# Main.net
KiCad netlist of a schematic drawn in Altium Designer
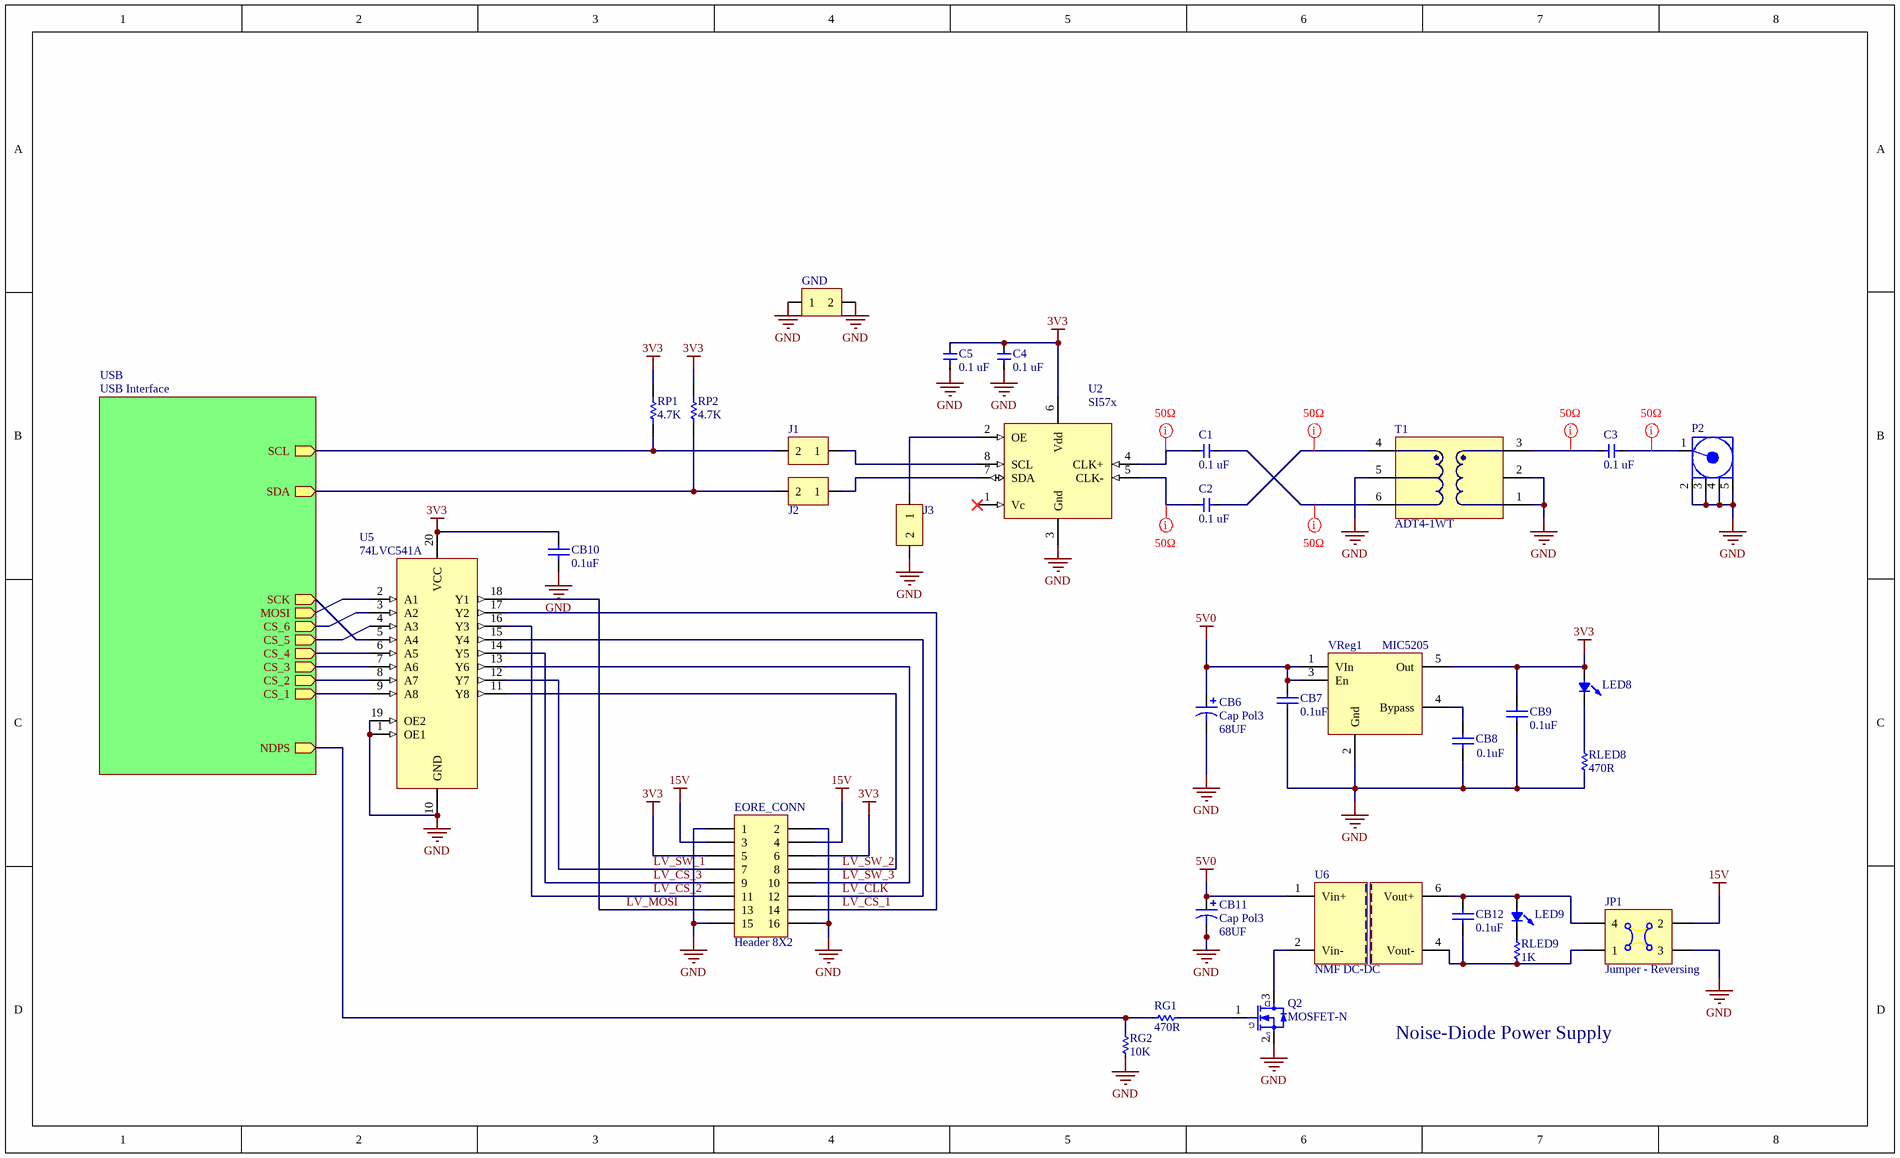
[diagram p0: Main.SchDoc]

(export (version "E")
  (design (tool "Eeschema 10.0.6"))
  (components
    (comp (ref "C1")
      (value "0.1 uF")
      (footprint "0603C")
      (description "SMT Cap")
      (fields (field (name "PUBLISHER") "Altium Limited"))
      (libsource (lib "Miscellaneous Devices") (part "Cap - SMT Small"))
    )
    (comp (ref "C2")
      (value "0.1 uF")
      (footprint "0603C")
      (description "SMT Cap")
      (fields (field (name "PUBLISHER") "Altium Limited"))
      (libsource (lib "Miscellaneous Devices") (part "Cap - SMT Small"))
    )
    (comp (ref "C3")
      (value "0.1 uF")
      (footprint "0603C")
      (description "SMT Cap")
      (fields (field (name "PUBLISHER") "Altium Limited"))
      (libsource (lib "Miscellaneous Devices") (part "Cap - SMT Small"))
    )
    (comp (ref "C4")
      (value "0.1 uF")
      (footprint "0603C")
      (description "SMT Cap")
      (fields (field (name "PUBLISHER") "Altium Limited"))
      (libsource (lib "Miscellaneous Devices") (part "Cap - SMT Small"))
    )
    (comp (ref "C5")
      (value "0.1 uF")
      (footprint "0603C")
      (description "SMT Cap")
      (fields (field (name "PUBLISHER") "Altium Limited"))
      (libsource (lib "Miscellaneous Devices") (part "Cap - SMT Small"))
    )
    (comp (ref "CB6")
      (value "Cap Pol3")
      (footprint "V")
      (description "KEMET T520 KO-CAP  Polymer SMT Tantalum")
      (fields (field (name "ALTIUM_VALUE") "68UF") (field (name "VOLTAGE") "10V"))
      (libsource (lib "Miscellaneous Devices") (part "Cap Pol3"))
    )
    (comp (ref "CB7")
      (value "0.1uF")
      (footprint "0603C")
      (description "Capacitor (Semiconductor SIM Model)")
      (fields (field (name "Comment") "Cap Semi") (field (name "PUBLISHER") "Altium Limited"))
      (libsource (lib "Miscellaneous Devices") (part "Cap Semi"))
    )
    (comp (ref "CB8")
      (value "0.1uF")
      (footprint "0603C")
      (description "Capacitor (Semiconductor SIM Model)")
      (fields (field (name "Comment") "Cap Semi") (field (name "PUBLISHER") "Altium Limited"))
      (libsource (lib "Miscellaneous Devices") (part "Cap Semi"))
    )
    (comp (ref "CB9")
      (value "0.1uF")
      (footprint "0603C")
      (description "Capacitor (Semiconductor SIM Model)")
      (fields (field (name "Comment") "Cap Semi") (field (name "PUBLISHER") "Altium Limited"))
      (libsource (lib "Miscellaneous Devices") (part "Cap Semi"))
    )
    (comp (ref "CB10")
      (value "0.1uF")
      (footprint "0603C")
      (description "Capacitor (Semiconductor SIM Model)")
      (fields (field (name "Comment") "Cap Semi") (field (name "PUBLISHER") "Altium Limited"))
      (libsource (lib "Miscellaneous Devices") (part "Cap Semi"))
    )
    (comp (ref "CB11")
      (value "Cap Pol3")
      (footprint "V")
      (description "KEMET T520 KO-CAP  Polymer SMT Tantalum")
      (fields (field (name "ALTIUM_VALUE") "68UF") (field (name "VOLTAGE") "10V"))
      (libsource (lib "Miscellaneous Devices") (part "Cap Pol3"))
    )
    (comp (ref "CB12")
      (value "0.1uF")
      (footprint "0603C")
      (description "Capacitor (Semiconductor SIM Model)")
      (fields (field (name "Comment") "Cap Semi") (field (name "PUBLISHER") "Altium Limited"))
      (libsource (lib "Miscellaneous Devices") (part "Cap Semi"))
    )
    (comp (ref "EORE_CONN")
      (value "Header 8X2")
      (footprint "SMT 16-pin rectangular header")
      (description "Header, 8-Pin, Dual row")
      (fields (field (name "PUBLISHER") "Altium Limited"))
      (libsource (lib "Miscellaneous Connectors") (part "Header 8X2"))
    )
    (comp (ref "GND")
      (value "Jumper")
      (footprint "HDR1X2")
      (description "Jumper - 2-Pin")
      (fields (field (name "PUBLISHER") "Altium Limited"))
      (libsource (lib "") (part "Jumper - 2 Pin_1"))
    )
    (comp (ref "J1")
      (value "Jumper")
      (footprint "HDR1X2")
      (description "Jumper - 2-Pin")
      (fields (field (name "PUBLISHER") "Altium Limited"))
      (libsource (lib "") (part "Jumper - 2 Pin_2"))
    )
    (comp (ref "J2")
      (value "Jumper")
      (footprint "HDR1X2")
      (description "Jumper - 2-Pin")
      (fields (field (name "PUBLISHER") "Altium Limited"))
      (libsource (lib "") (part "Jumper - 2 Pin_2"))
    )
    (comp (ref "J3")
      (value "Jumper")
      (footprint "HDR1X2")
      (description "Jumper - 2-Pin")
      (fields (field (name "PUBLISHER") "Altium Limited"))
      (libsource (lib "Miscellaneous Connectors") (part "Jumper - 2 Pin"))
    )
    (comp (ref "JP1")
      (value "Jumper - Reversing")
      (footprint "HDR2X2")
      (description "Reversing Jumper")
      (fields (field (name "PUBLISHER") "Altium Limited"))
      (libsource (lib "Miscellaneous Connectors") (part "Jumper - Reversing"))
    )
    (comp (ref "LED8")
      (value "LED0")
      (footprint "T1 LED")
      (description "T 1 3/4 LED")
      (fields (field (name "PUBLISHER") "Altium Limited"))
      (libsource (lib "Miscellaneous Devices") (part "LED0"))
    )
    (comp (ref "LED9")
      (value "LED0")
      (footprint "T1 LED")
      (description "T 1 3/4 LED")
      (fields (field (name "PUBLISHER") "Altium Limited"))
      (libsource (lib "Miscellaneous Devices") (part "LED0"))
    )
    (comp (ref "P2")
      (value "COAX-M")
      (footprint "SMA Jack - PCB Edge - MultiSize")
      (description "RF Coaxial PCB Connector, MMCX; Thru-Hole, Vertical Mount Plug,  50 Ohm Impedance")
      (fields (field (name "PUBLISHER") "Altium Limited"))
      (libsource (lib "Miscellaneous Connectors") (part "COAX-M"))
    )
    (comp (ref "Q2")
      (value "MOSFET-N")
      (footprint "SOT23-3N")
      (description "N-Channel MOSFET")
      (fields (field (name "PUBLISHER") "Altium Limited"))
      (libsource (lib "Miscellaneous Devices") (part "MOSFET-N"))
    )
    (comp (ref "RG1")
      (value "470R")
      (footprint "0603R")
      (description "Semiconductor Resistor")
      (fields (field (name "Comment") "Res Semi Small") (field (name "PUBLISHER") "Altium Limited"))
      (libsource (lib "Miscellaneous Devices") (part "Res Semi Small"))
    )
    (comp (ref "RG2")
      (value "10K")
      (footprint "0603R")
      (description "Semiconductor Resistor")
      (fields (field (name "Comment") "Res Semi Small") (field (name "PUBLISHER") "Altium Limited"))
      (libsource (lib "Miscellaneous Devices") (part "Res Semi Small"))
    )
    (comp (ref "RLED8")
      (value "470R")
      (footprint "0603R")
      (description "Semiconductor Resistor")
      (fields (field (name "Comment") "Res Semi Small") (field (name "PUBLISHER") "Altium Limited"))
      (libsource (lib "Miscellaneous Devices") (part "Res Semi Small"))
    )
    (comp (ref "RLED9")
      (value "1K")
      (footprint "0603R")
      (description "Semiconductor Resistor")
      (fields (field (name "Comment") "Res Semi Small") (field (name "PUBLISHER") "Altium Limited"))
      (libsource (lib "Miscellaneous Devices") (part "Res Semi Small"))
    )
    (comp (ref "RP1")
      (value "4.7K")
      (footprint "0603R")
      (description "Semiconductor Resistor")
      (fields (field (name "Comment") "Res Semi") (field (name "PUBLISHER") "Altium Limited"))
      (libsource (lib "Miscellaneous Devices") (part "Res Semi"))
    )
    (comp (ref "RP2")
      (value "4.7K")
      (footprint "0603R")
      (description "Semiconductor Resistor")
      (fields (field (name "Comment") "Res Semi") (field (name "PUBLISHER") "Altium Limited"))
      (libsource (lib "Miscellaneous Devices") (part "Res Semi"))
    )
    (comp (ref "T1")
      (value "ADT4-1WT")
      (footprint "CD542")
      (description "Surface Mount RF Transformer")
      (libsource (lib "RF Components") (part "ADT4-1WT"))
    )
    (comp (ref "U2")
      (value "SI57x")
      (footprint "SI57x")
      (description "10 MHZ TO 1.4 GHZ I2C PROGRAMMABLE XO/VCXO")
      (libsource (lib "RF Components") (part "SI570"))
    )
    (comp (ref "U5")
      (value "74LVC541A")
      (footprint "SOP65P780-20AN")
      (description "Octal buffer/line driver with 5 V tolerant inputs/outputs; 3-state")
      (libsource (lib "ICs") (part "74LVC541A"))
    )
    (comp (ref "U6")
      (value "NMF DC-DC")
      (footprint "SIL-6(A1)")
      (description "Murata NMF DC-DC - 1W, Single output")
      (libsource (lib "Unsorted") (part "Murata NMF DC-DC"))
    )
    (comp (ref "VReg1")
      (value "MIC5205")
      (footprint "SOT23-5AN")
      (description "150mA Low-Noise LDO Regulator")
      (libsource (lib "DAQ System") (part "MIC5205"))
    )
  )
  (nets
    (net (code "1") (name "/CS_1") (class "Default")
      (node (ref "U5") (pin "9") (pinfunction "A8_9") (pintype "input"))
    )
    (net (code "2") (name "/CS_2") (class "Default")
      (node (ref "U5") (pin "8") (pinfunction "A7_8") (pintype "input"))
    )
    (net (code "3") (name "/CS_3") (class "Default")
      (node (ref "U5") (pin "7") (pinfunction "A6_7") (pintype "input"))
    )
    (net (code "4") (name "/CS_4") (class "Default")
      (node (ref "U5") (pin "6") (pinfunction "A5_6") (pintype "input"))
    )
    (net (code "5") (name "/CS_5") (class "Default")
      (node (ref "U5") (pin "4") (pinfunction "A3_4") (pintype "input"))
    )
    (net (code "6") (name "/CS_6") (class "Default")
      (node (ref "U5") (pin "3") (pinfunction "A2_3") (pintype "input"))
    )
    (net (code "7") (name "/LV_CLK") (class "Default")
      (node (ref "EORE_CONN") (pin "12") (pinfunction "12_12") (pintype "passive"))
      (node (ref "U5") (pin "15") (pinfunction "Y4_15") (pintype "output"))
    )
    (net (code "8") (name "/LV_CS_1") (class "Default")
      (node (ref "EORE_CONN") (pin "14") (pinfunction "14_14") (pintype "passive"))
      (node (ref "U5") (pin "17") (pinfunction "Y2_17") (pintype "output"))
    )
    (net (code "9") (name "/LV_CS_2") (class "Default")
      (node (ref "EORE_CONN") (pin "11") (pinfunction "11_11") (pintype "passive"))
      (node (ref "U5") (pin "16") (pinfunction "Y3_16") (pintype "output"))
    )
    (net (code "10") (name "/LV_CS_3") (class "Default")
      (node (ref "EORE_CONN") (pin "9") (pinfunction "9_9") (pintype "passive"))
      (node (ref "U5") (pin "14") (pinfunction "Y5_14") (pintype "output"))
    )
    (net (code "11") (name "/LV_MOSI") (class "Default")
      (node (ref "EORE_CONN") (pin "13") (pinfunction "13_13") (pintype "passive"))
      (node (ref "U5") (pin "18") (pinfunction "Y1_18") (pintype "output"))
    )
    (net (code "12") (name "/LV_SW_1") (class "Default")
      (node (ref "EORE_CONN") (pin "7") (pinfunction "7_7") (pintype "passive"))
      (node (ref "U5") (pin "12") (pinfunction "Y7_12") (pintype "output"))
    )
    (net (code "13") (name "/LV_SW_2") (class "Default")
      (node (ref "EORE_CONN") (pin "8") (pinfunction "8_8") (pintype "passive"))
      (node (ref "U5") (pin "11") (pinfunction "Y8_11") (pintype "output"))
    )
    (net (code "14") (name "/LV_SW_3") (class "Default")
      (node (ref "EORE_CONN") (pin "10") (pinfunction "10_10") (pintype "passive"))
      (node (ref "U5") (pin "13") (pinfunction "Y6_13") (pintype "output"))
    )
    (net (code "15") (name "/MOSI") (class "Default")
      (node (ref "U5") (pin "2") (pinfunction "A1_2") (pintype "input"))
    )
    (net (code "16") (name "/NDPS") (class "Default")
      (node (ref "RG1") (pin "1") (pinfunction "1_1") (pintype "passive"))
      (node (ref "RG2") (pin "2") (pinfunction "2_2") (pintype "passive"))
    )
    (net (code "17") (name "/SCK") (class "Default")
      (node (ref "U5") (pin "5") (pinfunction "A4_5") (pintype "input"))
    )
    (net (code "18") (name "/SCL") (class "Default")
      (node (ref "J1") (pin "2") (pinfunction "2_2") (pintype "passive"))
      (node (ref "RP1") (pin "1") (pinfunction "1_1") (pintype "passive"))
    )
    (net (code "19") (name "/SDA") (class "Default")
      (node (ref "J2") (pin "2") (pinfunction "2_2") (pintype "passive"))
      (node (ref "RP2") (pin "1") (pinfunction "1_1") (pintype "passive"))
    )
    (net (code "20") (name "3V3") (class "Default")
      (node (ref "C4") (pin "2") (pinfunction "2_2") (pintype "passive"))
      (node (ref "C5") (pin "2") (pinfunction "2_2") (pintype "passive"))
      (node (ref "CB10") (pin "2") (pinfunction "2_2") (pintype "passive"))
      (node (ref "CB9") (pin "2") (pinfunction "2_2") (pintype "passive"))
      (node (ref "EORE_CONN") (pin "5") (pinfunction "5_5") (pintype "passive"))
      (node (ref "EORE_CONN") (pin "6") (pinfunction "6_6") (pintype "passive"))
      (node (ref "LED8") (pin "1") (pinfunction "1_1") (pintype "passive"))
      (node (ref "RP1") (pin "2") (pinfunction "2_2") (pintype "passive"))
      (node (ref "RP2") (pin "2") (pinfunction "2_2") (pintype "passive"))
      (node (ref "U2") (pin "6") (pinfunction "Vdd_6") (pintype "power_in"))
      (node (ref "U5") (pin "20") (pinfunction "VCC_20") (pintype "power_in"))
      (node (ref "VReg1") (pin "5") (pinfunction "Out_5") (pintype "power_in"))
    )
    (net (code "21") (name "5V0") (class "Default")
      (node (ref "CB11") (pin "1") (pinfunction "1_1") (pintype "passive"))
      (node (ref "CB6") (pin "1") (pinfunction "1_1") (pintype "passive"))
      (node (ref "CB7") (pin "2") (pinfunction "2_2") (pintype "passive"))
      (node (ref "U6") (pin "1") (pinfunction "Vin+_1") (pintype "power_in"))
      (node (ref "VReg1") (pin "1") (pinfunction "VIn_1") (pintype "power_in"))
      (node (ref "VReg1") (pin "3") (pinfunction "En_3") (pintype "power_in"))
    )
    (net (code "22") (name "15V") (class "Default")
      (node (ref "EORE_CONN") (pin "3") (pinfunction "3_3") (pintype "passive"))
      (node (ref "EORE_CONN") (pin "4") (pinfunction "4_4") (pintype "passive"))
      (node (ref "JP1") (pin "2") (pinfunction "2_2") (pintype "passive"))
    )
    (net (code "23") (name "GND") (class "Default")
      (node (ref "C4") (pin "1") (pinfunction "1_1") (pintype "passive"))
      (node (ref "C5") (pin "1") (pinfunction "1_1") (pintype "passive"))
      (node (ref "CB10") (pin "1") (pinfunction "1_1") (pintype "passive"))
      (node (ref "CB11") (pin "2") (pinfunction "2_2") (pintype "passive"))
      (node (ref "CB6") (pin "2") (pinfunction "2_2") (pintype "passive"))
      (node (ref "CB7") (pin "1") (pinfunction "1_1") (pintype "passive"))
      (node (ref "CB8") (pin "1") (pinfunction "1_1") (pintype "passive"))
      (node (ref "CB9") (pin "1") (pinfunction "1_1") (pintype "passive"))
      (node (ref "EORE_CONN") (pin "1") (pinfunction "1_1") (pintype "passive"))
      (node (ref "EORE_CONN") (pin "15") (pinfunction "15_15") (pintype "passive"))
      (node (ref "EORE_CONN") (pin "16") (pinfunction "16_16") (pintype "passive"))
      (node (ref "EORE_CONN") (pin "2") (pinfunction "2_2") (pintype "passive"))
      (node (ref "GND") (pin "1") (pinfunction "1_1") (pintype "passive"))
      (node (ref "GND") (pin "2") (pinfunction "2_2") (pintype "passive"))
      (node (ref "J3") (pin "2") (pinfunction "2_2") (pintype "passive"))
      (node (ref "JP1") (pin "3") (pinfunction "3_3") (pintype "passive"))
      (node (ref "P2") (pin "2") (pinfunction "GND_2") (pintype "power_in"))
      (node (ref "P2") (pin "3") (pinfunction "GND_3") (pintype "power_in"))
      (node (ref "P2") (pin "4") (pinfunction "GND_4") (pintype "power_in"))
      (node (ref "P2") (pin "5") (pinfunction "GND_5") (pintype "power_in"))
      (node (ref "Q2") (pin "2") (pinfunction "S_2") (pintype "passive"))
      (node (ref "RG2") (pin "1") (pinfunction "1_1") (pintype "passive"))
      (node (ref "RLED8") (pin "2") (pinfunction "2_2") (pintype "passive"))
      (node (ref "T1") (pin "1") (pinfunction "Input_1") (pintype "passive"))
      (node (ref "T1") (pin "2") (pinfunction "Gnd_2") (pintype "power_in"))
      (node (ref "T1") (pin "5") (pinfunction "Termination_5") (pintype "passive"))
      (node (ref "U2") (pin "3") (pinfunction "Gnd_3") (pintype "power_in"))
      (node (ref "U5") (pin "1") (pinfunction "OE1_1") (pintype "input"))
      (node (ref "U5") (pin "10") (pinfunction "GND_10") (pintype "power_in"))
      (node (ref "U5") (pin "19") (pinfunction "OE2_19") (pintype "input"))
      (node (ref "VReg1") (pin "2") (pinfunction "Gnd_2") (pintype "power_in"))
    )
    (net (code "24") (name "Net-(C2-Pad2)") (class "Default")
      (node (ref "C2") (pin "2") (pinfunction "2_2") (pintype "passive"))
      (node (ref "T1") (pin "4") (pinfunction "Termination_4") (pintype "passive"))
    )
    (net (code "25") (name "Net-(LED8-Pad2)") (class "Default")
      (node (ref "LED8") (pin "2") (pinfunction "2_2") (pintype "passive"))
      (node (ref "RLED8") (pin "1") (pinfunction "1_1") (pintype "passive"))
    )
    (net (code "26") (name "Net-(LED9-Pad2)") (class "Default")
      (node (ref "LED9") (pin "2") (pinfunction "2_2") (pintype "passive"))
      (node (ref "RLED9") (pin "1") (pinfunction "1_1") (pintype "passive"))
    )
    (net (code "27") (name "Net-(P2-Signal)") (class "Default")
      (node (ref "C3") (pin "2") (pinfunction "2_2") (pintype "passive"))
      (node (ref "P2") (pin "1") (pinfunction "Signal_1") (pintype "passive"))
    )
    (net (code "28") (name "Net-(Q2-D)") (class "Default")
      (node (ref "Q2") (pin "3") (pinfunction "D_3") (pintype "passive"))
      (node (ref "U6") (pin "2") (pinfunction "Vin-_2") (pintype "power_in"))
    )
    (net (code "29") (name "Net-(Q2-G)") (class "Default")
      (node (ref "Q2") (pin "1") (pinfunction "G_1") (pintype "passive"))
      (node (ref "RG1") (pin "2") (pinfunction "2_2") (pintype "passive"))
    )
    (net (code "30") (name "Net-(T1-Coupled)") (class "Default")
      (node (ref "C3") (pin "1") (pinfunction "1_1") (pintype "passive"))
      (node (ref "T1") (pin "3") (pinfunction "Coupled_3") (pintype "passive"))
    )
    (net (code "31") (name "Net-(T1-Output)") (class "Default")
      (node (ref "C1") (pin "2") (pinfunction "2_2") (pintype "passive"))
      (node (ref "T1") (pin "6") (pinfunction "Output_6") (pintype "passive"))
    )
    (net (code "32") (name "Net-(U2-CLK+)") (class "Default")
      (node (ref "C1") (pin "1") (pinfunction "1_1") (pintype "passive"))
      (node (ref "U2") (pin "4") (pinfunction "CLK+_4") (pintype "input"))
    )
    (net (code "33") (name "Net-(U2-CLK-)") (class "Default")
      (node (ref "C2") (pin "1") (pinfunction "1_1") (pintype "passive"))
      (node (ref "U2") (pin "5") (pinfunction "CLK-_5") (pintype "input"))
    )
    (net (code "34") (name "Net-(U2-OE)") (class "Default")
      (node (ref "J3") (pin "1") (pinfunction "1_1") (pintype "passive"))
      (node (ref "U2") (pin "2") (pinfunction "OE_2") (pintype "input"))
    )
    (net (code "35") (name "Net-(U2-SCL)") (class "Default")
      (node (ref "J1") (pin "1") (pinfunction "1_1") (pintype "passive"))
      (node (ref "U2") (pin "8") (pinfunction "SCL_8") (pintype "input"))
    )
    (net (code "36") (name "Net-(U2-SDA)") (class "Default")
      (node (ref "J2") (pin "1") (pinfunction "1_1") (pintype "passive"))
      (node (ref "U2") (pin "7") (pinfunction "SDA_7") (pintype "bidirectional"))
    )
    (net (code "37") (name "Net-(U6-Vout+)") (class "Default")
      (node (ref "CB12") (pin "2") (pinfunction "2_2") (pintype "passive"))
      (node (ref "JP1") (pin "4") (pinfunction "4_4") (pintype "passive"))
      (node (ref "LED9") (pin "1") (pinfunction "1_1") (pintype "passive"))
      (node (ref "U6") (pin "6") (pinfunction "Vout+_6") (pintype "power_in"))
    )
    (net (code "38") (name "Net-(U6-Vout-)") (class "Default")
      (node (ref "CB12") (pin "1") (pinfunction "1_1") (pintype "passive"))
      (node (ref "JP1") (pin "1") (pinfunction "1_1") (pintype "passive"))
      (node (ref "RLED9") (pin "2") (pinfunction "2_2") (pintype "passive"))
      (node (ref "U6") (pin "4") (pinfunction "Vout-_4") (pintype "power_in"))
    )
    (net (code "39") (name "Net-(VReg1-Bypass)") (class "Default")
      (node (ref "CB8") (pin "2") (pinfunction "2_2") (pintype "passive"))
      (node (ref "VReg1") (pin "4") (pinfunction "Bypass_4") (pintype "power_in"))
    )
    (net (code "40") (name "unconnected-(U2-Vc-Pad1)") (class "Default")
      (node (ref "U2") (pin "1") (pinfunction "Vc_1") (pintype "input+no_connect"))
    )
  )
)
